# HM11_Breakout.net
KiCad netlist of a schematic drawn in EAGLE
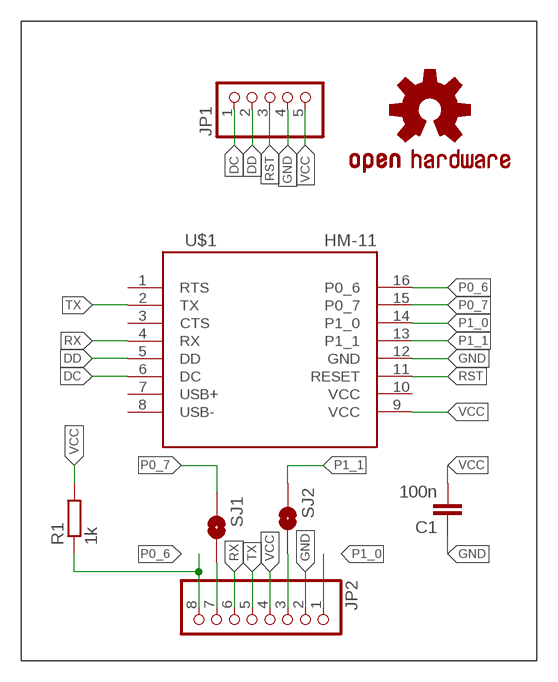
[diagram p0: schematic, sheet 1]

(export (version "E")
  (design (tool "Eeschema 10.0.6"))
  (components
    (comp (ref "C1")
      (value "100n")
      (footprint "eagle-import:1206")
      (libsource (lib "eagle-import") (part "C-EU1206"))
    )
    (comp (ref "JP1")
      (value "PINHD-1X5")
      (footprint "eagle-import:1X05")
      (libsource (lib "eagle-import") (part "PINHD-1X5"))
    )
    (comp (ref "JP2")
      (value "PINHD-1X8")
      (footprint "eagle-import:1X08")
      (libsource (lib "eagle-import") (part "PINHD-1X8"))
    )
    (comp (ref "LOGO1")
      (value "OSHW-LOGOM")
      (footprint "eagle-import:OSHW-LOGO-M")
      (libsource (lib "eagle-import") (part "OSHW-LOGOM"))
    )
    (comp (ref "R1")
      (value "1k")
      (footprint "eagle-import:R1206")
      (libsource (lib "eagle-import") (part "R-EU_R1206"))
    )
    (comp (ref "SJ1")
      (value "SOLDERJUMPERTRACE")
      (footprint "eagle-import:SJ_2S-TRACE")
      (libsource (lib "eagle-import") (part "SOLDERJUMPERTRACE"))
    )
    (comp (ref "SJ2")
      (value "SOLDERJUMPERTRACE")
      (footprint "eagle-import:SJ_2S-TRACE")
      (libsource (lib "eagle-import") (part "SOLDERJUMPERTRACE"))
    )
    (comp (ref "U$1")
      (value "HM-11")
      (footprint "eagle-import:HM-11")
      (libsource (lib "eagle-import") (part "HM-11"))
    )
  )
  (nets
    (net (code "1") (name "DC") (class "Default")
      (node (ref "JP1") (pin "1") (pinfunction "1_1") (pintype "passive"))
      (node (ref "U$1") (pin "6") (pinfunction "DC_6") (pintype "bidirectional"))
    )
    (net (code "2") (name "DD") (class "Default")
      (node (ref "JP1") (pin "2") (pinfunction "2_2") (pintype "passive"))
      (node (ref "U$1") (pin "5") (pinfunction "DD_5") (pintype "bidirectional"))
    )
    (net (code "3") (name "GND") (class "Default")
      (node (ref "C1") (pin "1") (pinfunction "1_1") (pintype "passive"))
      (node (ref "JP1") (pin "4") (pinfunction "4_4") (pintype "passive"))
      (node (ref "JP2") (pin "2") (pinfunction "2_2") (pintype "passive"))
      (node (ref "U$1") (pin "12") (pinfunction "GND_12") (pintype "bidirectional"))
    )
    (net (code "4") (name "Net-(JP2-Pad3)") (class "Default")
      (node (ref "JP2") (pin "3") (pinfunction "3_3") (pintype "passive"))
      (node (ref "SJ2") (pin "1") (pinfunction "1_1") (pintype "passive"))
    )
    (net (code "5") (name "Net-(JP2-Pad7)") (class "Default")
      (node (ref "JP2") (pin "7") (pinfunction "7_7") (pintype "passive"))
      (node (ref "SJ1") (pin "1") (pinfunction "1_1") (pintype "passive"))
    )
    (net (code "6") (name "P0_6") (class "Default")
      (node (ref "JP2") (pin "8") (pinfunction "8_8") (pintype "passive"))
      (node (ref "R1") (pin "1") (pinfunction "1_1") (pintype "passive"))
      (node (ref "U$1") (pin "16") (pinfunction "P0_6_16") (pintype "bidirectional"))
    )
    (net (code "7") (name "P0_7") (class "Default")
      (node (ref "SJ1") (pin "2") (pinfunction "2_2") (pintype "passive"))
      (node (ref "U$1") (pin "15") (pinfunction "P0_7_15") (pintype "bidirectional"))
    )
    (net (code "8") (name "P1_0") (class "Default")
      (node (ref "JP2") (pin "1") (pinfunction "1_1") (pintype "passive"))
      (node (ref "U$1") (pin "14") (pinfunction "P1_0_14") (pintype "bidirectional"))
    )
    (net (code "9") (name "P1_1") (class "Default")
      (node (ref "SJ2") (pin "2") (pinfunction "2_2") (pintype "passive"))
      (node (ref "U$1") (pin "13") (pinfunction "P1_1_13") (pintype "bidirectional"))
    )
    (net (code "10") (name "RST") (class "Default")
      (node (ref "JP1") (pin "3") (pinfunction "3_3") (pintype "passive"))
      (node (ref "U$1") (pin "11") (pinfunction "RESET_11") (pintype "bidirectional"))
    )
    (net (code "11") (name "RX") (class "Default")
      (node (ref "JP2") (pin "6") (pinfunction "6_6") (pintype "passive"))
      (node (ref "U$1") (pin "4") (pinfunction "RX_4") (pintype "bidirectional"))
    )
    (net (code "12") (name "TX") (class "Default")
      (node (ref "JP2") (pin "5") (pinfunction "5_5") (pintype "passive"))
      (node (ref "U$1") (pin "2") (pinfunction "TX_2") (pintype "bidirectional"))
    )
    (net (code "13") (name "VCC") (class "Default")
      (node (ref "C1") (pin "2") (pinfunction "2_2") (pintype "passive"))
      (node (ref "JP1") (pin "5") (pinfunction "5_5") (pintype "passive"))
      (node (ref "JP2") (pin "4") (pinfunction "4_4") (pintype "passive"))
      (node (ref "R1") (pin "2") (pinfunction "2_2") (pintype "passive"))
      (node (ref "U$1") (pin "9") (pinfunction "VCC_9") (pintype "bidirectional"))
    )
    (net (code "14") (name "unconnected-(U$1-CTS-Pad3)") (class "Default")
      (node (ref "U$1") (pin "3") (pinfunction "CTS_3") (pintype "bidirectional"))
    )
    (net (code "15") (name "unconnected-(U$1-RTS-Pad1)") (class "Default")
      (node (ref "U$1") (pin "1") (pinfunction "RTS_1") (pintype "bidirectional"))
    )
    (net (code "16") (name "unconnected-(U$1-USB+-Pad7)") (class "Default")
      (node (ref "U$1") (pin "7") (pinfunction "USB+_7") (pintype "bidirectional"))
    )
    (net (code "17") (name "unconnected-(U$1-USB--Pad8)") (class "Default")
      (node (ref "U$1") (pin "8") (pinfunction "USB-_8") (pintype "bidirectional"))
    )
    (net (code "18") (name "unconnected-(U$1-VCC-Pad10)") (class "Default")
      (node (ref "U$1") (pin "10") (pinfunction "VCC_10") (pintype "bidirectional"))
    )
  )
)
